# Sheet1.net
KiCad netlist of a schematic drawn in Altium Designer
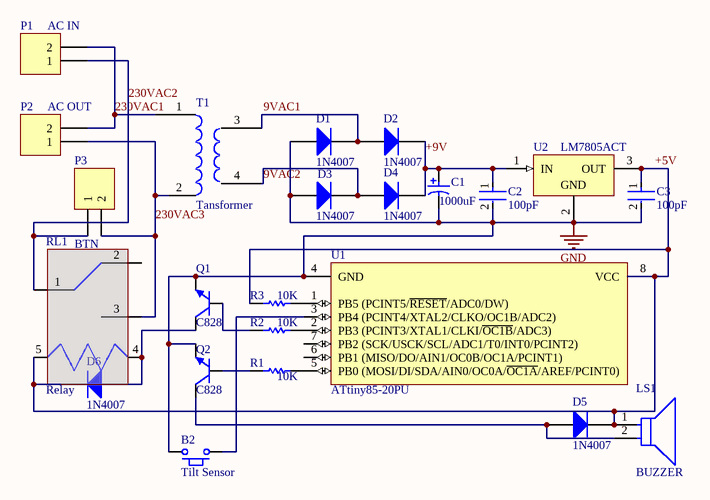
[diagram p0: Sheet1.SchDoc]

(export (version "E")
  (design (tool "Eeschema 10.0.6"))
  (components
    (comp (ref "B2")
      (value "Tilt Sensor")
      (footprint "PUSH_BTN")
      (libsource (lib "Common Parts") (part "Push Button"))
    )
    (comp (ref "C1")
      (value "ECA1EM102")
      (footprint "CAPPR65-500-2000X1000X2200")
      (description "Aluminum Electrolytic Capacitor, 1000 uF, +/- 20%, 25 V, -40 to 85 degC, 2-Pin THD, RoHS, Bulk")
      (fields
        (field (name "MANUFACTURER") "Panasonic")
        (field (name "TOLERANCE") "20%")
        (field (name "CAPACITANCE") "1000uF")
      )
      (libsource (lib "Altium Content Vault") (part "CAP-P-2"))
    )
    (comp (ref "C2")
      (value "RCE5C1H101J0DBH03A")
      (footprint "FP-RCE0DB-MFG")
      (description "Cap Ceramic 100pF 50V C0G ±5% Radial 2.5mm +125°C Ammo Pack")
      (fields (field (name "TOLERANCE") "5%") (field (name "CAPACITANCE") "100pF"))
      (libsource (lib "Altium Content Vault") (part "b4654b650e69147ec39a6b967a45e02"))
    )
    (comp (ref "C3")
      (value "RCE5C1H101J0DBH03A")
      (footprint "FP-RCE0DB-MFG")
      (description "Cap Ceramic 100pF 50V C0G ±5% Radial 2.5mm +125°C Ammo Pack")
      (fields (field (name "TOLERANCE") "5%") (field (name "CAPACITANCE") "100pF"))
      (libsource (lib "Altium Content Vault") (part "b4654b650e69147ec39a6b967a45e02"))
    )
    (comp (ref "D1")
      (value "1N4007")
      (footprint "1N4007")
      (description "1 Amp General Purpose Rectifier")
      (fields (field (name "PUBLISHER") "Altium Limited"))
      (libsource (lib "Miscellaneous Devices") (part "Diode 1N4007"))
    )
    (comp (ref "D2")
      (value "1N4007")
      (footprint "1N4007")
      (description "1 Amp General Purpose Rectifier")
      (fields (field (name "PUBLISHER") "Altium Limited"))
      (libsource (lib "Miscellaneous Devices") (part "Diode 1N4007"))
    )
    (comp (ref "D3")
      (value "1N4007")
      (footprint "1N4007")
      (description "1 Amp General Purpose Rectifier")
      (fields (field (name "PUBLISHER") "Altium Limited"))
      (libsource (lib "Miscellaneous Devices") (part "Diode 1N4007"))
    )
    (comp (ref "D4")
      (value "1N4007")
      (footprint "1N4007")
      (description "1 Amp General Purpose Rectifier")
      (fields (field (name "PUBLISHER") "Altium Limited"))
      (libsource (lib "Miscellaneous Devices") (part "Diode 1N4007"))
    )
    (comp (ref "D5")
      (value "1N4007")
      (footprint "1N4007")
      (description "1 Amp General Purpose Rectifier")
      (fields (field (name "PUBLISHER") "Altium Limited"))
      (libsource (lib "Miscellaneous Devices") (part "Diode 1N4007"))
    )
    (comp (ref "D6")
      (value "1N4007")
      (footprint "1N4007")
      (description "1 Amp General Purpose Rectifier")
      (fields (field (name "PUBLISHER") "Altium Limited"))
      (libsource (lib "Miscellaneous Devices") (part "Diode 1N4007"))
    )
    (comp (ref "LS1")
      (value "BUZZER")
      (footprint "FP-MCKPX-G1203A-K4056-MFG")
      (fields
        (field (name "MANUFACTURER PART NUMBER") "MCKPX-G1203A-K4056")
        (field (name "MANUFACTURER") "Multicomp Pro")
        (field (name "OCTOPART") "https://octopart.com/mckpx-g1203a-k4056-multicomp-12157154")
      )
      (libsource (lib "Altium Content Vault") (part "1973c4b650225fd2ddacaff6b763965"))
    )
    (comp (ref "P1")
      (value "AC IN")
      (footprint "H2_PWR_AC")
      (description "Header, 2-Pin")
      (fields (field (name "PUBLISHER") "Altium Limited"))
      (libsource (lib "Footprints_lib") (part "Header 2"))
    )
    (comp (ref "P2")
      (value "AC OUT")
      (footprint "H2_PWR_AC")
      (description "Header, 2-Pin")
      (fields (field (name "PUBLISHER") "Altium Limited"))
      (libsource (lib "Footprints_lib") (part "Header 2"))
    )
    (comp (ref "P3")
      (value "BTN")
      (footprint "H2_PWR_AC")
      (description "Header, 2-Pin")
      (fields (field (name "PUBLISHER") "Altium Limited"))
      (libsource (lib "") (part "Header 2_1"))
    )
    (comp (ref "Q1")
      (value "C828")
      (footprint "TO-92_ONS")
      (description "NPN General Purpose Transistor")
      (fields (field (name "PUBLISHER") "Altium Limited"))
      (libsource (lib "Common Parts") (part "C828"))
    )
    (comp (ref "Q2")
      (value "C828")
      (footprint "TO-92_ONS")
      (description "NPN General Purpose Transistor")
      (fields (field (name "PUBLISHER") "Altium Limited"))
      (libsource (lib "Common Parts") (part "C828"))
    )
    (comp (ref "R1")
      (value "10K")
      (footprint "RES")
      (description "Resistor")
      (fields (field (name "PUBLISHER") "Altium Limited"))
      (libsource (lib "Common Parts") (part "Res1"))
    )
    (comp (ref "R2")
      (value "10K")
      (footprint "RES")
      (description "Resistor")
      (fields (field (name "PUBLISHER") "Altium Limited"))
      (libsource (lib "Common Parts") (part "Res1"))
    )
    (comp (ref "R3")
      (value "10K")
      (footprint "RES")
      (description "Resistor")
      (fields (field (name "PUBLISHER") "Altium Limited"))
      (libsource (lib "Common Parts") (part "Res1"))
    )
    (comp (ref "RL1") (value "Relay") (footprint "Relay") (libsource (lib "Common Parts") (part "Relay")))
    (comp (ref "T1")
      (value "Tansformer")
      (footprint "TRANSFORMER")
      (libsource (lib "Common Parts") (part "Tansformer"))
    )
    (comp (ref "U1")
      (value "ATtiny85-20PU")
      (footprint "8P3")
      (libsource (lib "Altium Content Vault") (part "MC-8B-ATT25-IL8"))
    )
    (comp (ref "U2")
      (value "LM7805ACT")
      (footprint "FAIR-TO-220-3")
      (description "Positive Voltage Regulator, 5 V, 1 A, 0 to 125 degC, 3-Pin TO-220, RoHS, Tube")
      (fields (field (name "MANUFACTURER") "Fairchild"))
      (libsource (lib "Altium Content Vault") (part "FAIR-LM7805CT-TO220-3"))
    )
  )
  (nets
    (net (code "1") (name "/+5V") (class "Default")
      (node (ref "C3") (pin "1") (pinfunction "1_1") (pintype "passive"))
      (node (ref "D5") (pin "2") (pinfunction "K_2") (pintype "passive"))
      (node (ref "D6") (pin "2") (pinfunction "K_2") (pintype "passive"))
      (node (ref "LS1") (pin "1") (pinfunction "C_1") (pintype "passive"))
      (node (ref "R3") (pin "1") (pinfunction "1_1") (pintype "passive"))
      (node (ref "RL1") (pin "5") (pinfunction "5_5") (pintype "passive"))
      (node (ref "U1") (pin "8") (pinfunction "VCC_8") (pintype "power_in"))
      (node (ref "U2") (pin "3") (pinfunction "OUT_3") (pintype "passive"))
    )
    (net (code "2") (name "/+9V") (class "Default")
      (node (ref "C1") (pin "1") (pinfunction "1_1") (pintype "passive"))
      (node (ref "C2") (pin "1") (pinfunction "1_1") (pintype "passive"))
      (node (ref "D2") (pin "2") (pinfunction "K_2") (pintype "passive"))
      (node (ref "D4") (pin "2") (pinfunction "K_2") (pintype "passive"))
      (node (ref "U2") (pin "1") (pinfunction "IN_1") (pintype "input"))
    )
    (net (code "3") (name "/9VAC1") (class "Default")
      (node (ref "D1") (pin "2") (pinfunction "K_2") (pintype "passive"))
      (node (ref "D2") (pin "1") (pinfunction "A_1") (pintype "passive"))
      (node (ref "T1") (pin "3") (pinfunction "DC1_3") (pintype "passive"))
    )
    (net (code "4") (name "/9VAC2") (class "Default")
      (node (ref "D3") (pin "2") (pinfunction "K_2") (pintype "passive"))
      (node (ref "D4") (pin "1") (pinfunction "A_1") (pintype "passive"))
      (node (ref "T1") (pin "4") (pinfunction "DC2_4") (pintype "passive"))
    )
    (net (code "5") (name "/230VAC1") (class "Default")
      (node (ref "P1") (pin "2") (pinfunction "2_2") (pintype "passive"))
      (node (ref "P2") (pin "2") (pinfunction "2_2") (pintype "passive"))
      (node (ref "T1") (pin "1") (pinfunction "AC1_1") (pintype "passive"))
    )
    (net (code "6") (name "/230VAC2") (class "Default")
      (node (ref "P1") (pin "1") (pinfunction "1_1") (pintype "passive"))
      (node (ref "P3") (pin "1") (pinfunction "1_1") (pintype "passive"))
      (node (ref "RL1") (pin "1") (pinfunction "1_1") (pintype "passive"))
    )
    (net (code "7") (name "/230VAC3") (class "Default")
      (node (ref "P2") (pin "1") (pinfunction "1_1") (pintype "passive"))
      (node (ref "P3") (pin "2") (pinfunction "2_2") (pintype "passive"))
      (node (ref "RL1") (pin "3") (pinfunction "3_3") (pintype "passive"))
      (node (ref "T1") (pin "2") (pinfunction "AC2_2") (pintype "passive"))
    )
    (net (code "8") (name "GND") (class "Default")
      (node (ref "B2") (pin "1") (pinfunction "1_1") (pintype "passive"))
      (node (ref "C1") (pin "2") (pinfunction "2_2") (pintype "passive"))
      (node (ref "C2") (pin "2") (pinfunction "2_2") (pintype "passive"))
      (node (ref "C3") (pin "2") (pinfunction "2_2") (pintype "passive"))
      (node (ref "D1") (pin "1") (pinfunction "A_1") (pintype "passive"))
      (node (ref "D3") (pin "1") (pinfunction "A_1") (pintype "passive"))
      (node (ref "Q1") (pin "1") (pinfunction "E_1") (pintype "passive"))
      (node (ref "Q2") (pin "1") (pinfunction "E_1") (pintype "passive"))
      (node (ref "U1") (pin "4") (pinfunction "GND_4") (pintype "power_in"))
      (node (ref "U2") (pin "2") (pinfunction "GND_2") (pintype "power_in"))
    )
    (net (code "9") (name "Net-(D5-A)") (class "Default")
      (node (ref "D5") (pin "1") (pinfunction "A_1") (pintype "passive"))
      (node (ref "LS1") (pin "2") (pinfunction "A_2") (pintype "passive"))
      (node (ref "Q2") (pin "2") (pinfunction "C_2") (pintype "passive"))
    )
    (net (code "10") (name "Net-(D6-A)") (class "Default")
      (node (ref "D6") (pin "1") (pinfunction "A_1") (pintype "passive"))
      (node (ref "Q1") (pin "2") (pinfunction "C_2") (pintype "passive"))
      (node (ref "RL1") (pin "4") (pinfunction "4_4") (pintype "passive"))
    )
    (net (code "11") (name "Net-(Q1-B)") (class "Default")
      (node (ref "Q1") (pin "3") (pinfunction "B_3") (pintype "passive"))
      (node (ref "R2") (pin "1") (pinfunction "1_1") (pintype "passive"))
    )
    (net (code "12") (name "Net-(Q2-B)") (class "Default")
      (node (ref "Q2") (pin "3") (pinfunction "B_3") (pintype "passive"))
      (node (ref "R1") (pin "1") (pinfunction "1_1") (pintype "passive"))
    )
    (net (code "13") (name "Net-(U1-PB0_(MOSI{slash}DI{slash}SDA{slash}AIN0{slash}OC0A{slash}~{OC1A}{slash}AREF{slash}PCINT0))") (class "Default")
      (node (ref "R1") (pin "2") (pinfunction "2_2") (pintype "passive"))
      (node (ref "U1") (pin "5") (pinfunction "PB0_(MOSI/DI/SDA/AIN0/OC0A/~{OC1A}/AREF/PCINT0)_5") (pintype "bidirectional"))
    )
    (net (code "14") (name "Net-(U1-PB3_(PCINT3{slash}XTAL1{slash}CLKI{slash}~{OC1B}{slash}ADC3))") (class "Default")
      (node (ref "R2") (pin "2") (pinfunction "2_2") (pintype "passive"))
      (node (ref "U1") (pin "2") (pinfunction "PB3_(PCINT3/XTAL1/CLKI/~{OC1B}/ADC3)_2") (pintype "bidirectional"))
    )
    (net (code "15") (name "Net-(U1-PB4_(PCINT4{slash}XTAL2{slash}CLKO{slash}OC1B{slash}ADC2))") (class "Default")
      (node (ref "B2") (pin "2") (pinfunction "2_2") (pintype "passive"))
      (node (ref "U1") (pin "3") (pinfunction "PB4_(PCINT4/XTAL2/CLKO/OC1B/ADC2)_3") (pintype "bidirectional"))
    )
    (net (code "16") (name "Net-(U1-PB5_(PCINT5{slash}~{RESET}{slash}ADC0{slash}DW))") (class "Default")
      (node (ref "R3") (pin "2") (pinfunction "2_2") (pintype "passive"))
      (node (ref "U1") (pin "1") (pinfunction "PB5_(PCINT5/~{RESET}/ADC0/DW)_1") (pintype "bidirectional"))
    )
    (net (code "17") (name "unconnected-(RL1-Pad2)") (class "Default")
      (node (ref "RL1") (pin "2") (pinfunction "2_2") (pintype "passive"))
    )
    (net (code "18") (name "unconnected-(U1-PB1_(MISO{slash}DO{slash}AIN1{slash}OC0B{slash}OC1A{slash}PCINT1)-Pad6)") (class "Default")
      (node (ref "U1") (pin "6") (pinfunction "PB1_(MISO/DO/AIN1/OC0B/OC1A/PCINT1)_6") (pintype "bidirectional"))
    )
    (net (code "19") (name "unconnected-(U1-PB2_(SCK{slash}USCK{slash}SCL{slash}ADC1{slash}T0{slash}INT0{slash}PCINT2)-Pad7)") (class "Default")
      (node (ref "U1") (pin "7") (pinfunction "PB2_(SCK/USCK/SCL/ADC1/T0/INT0/PCINT2)_7") (pintype "bidirectional"))
    )
  )
)
